# uno.net
KiCad netlist of a schematic drawn in EAGLE
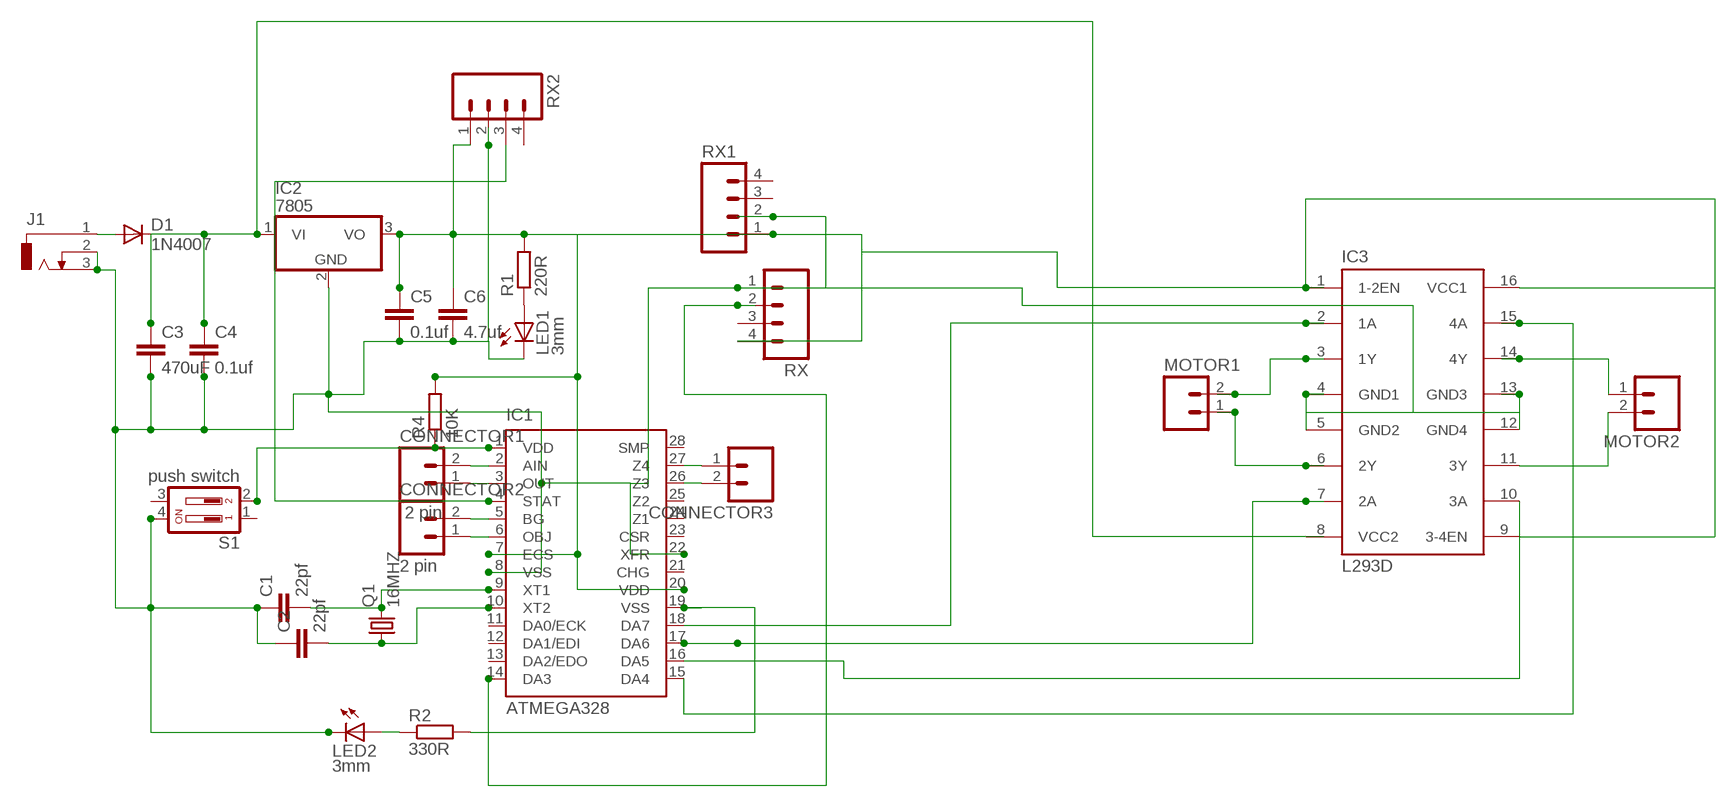
[diagram p0: schematic, sheet 1]

(export (version "E")
  (design (tool "Eeschema 10.0.6"))
  (components
    (comp (ref "C1")
      (value "22pf")
      (footprint "eagle-import:C2.5-2")
      (libsource (lib "eagle-import") (part "C2.5/2"))
    )
    (comp (ref "C2")
      (value "22pf")
      (footprint "eagle-import:C2.5-2")
      (libsource (lib "eagle-import") (part "C2.5/2"))
    )
    (comp (ref "C3")
      (value "470uF")
      (footprint "eagle-import:C2.5-2")
      (libsource (lib "eagle-import") (part "C2.5/2"))
    )
    (comp (ref "C4")
      (value "0.1uf")
      (footprint "eagle-import:C2.5-2")
      (libsource (lib "eagle-import") (part "C2.5/2"))
    )
    (comp (ref "C5")
      (value "0.1uf")
      (footprint "eagle-import:C2.5-2")
      (libsource (lib "eagle-import") (part "C2.5/2"))
    )
    (comp (ref "C6")
      (value "4.7uf")
      (footprint "eagle-import:C2.5-2")
      (libsource (lib "eagle-import") (part "C2.5/2"))
    )
    (comp (ref "CONNECTOR1")
      (value "2 pin")
      (footprint "eagle-import:02P")
      (fields (field (name "OC_FARNELL") "unknown") (field (name "OC_NEWARK") "unknown"))
      (libsource (lib "eagle-import") (part "M02"))
    )
    (comp (ref "CONNECTOR2")
      (value "2 pin")
      (footprint "eagle-import:02P")
      (fields (field (name "OC_FARNELL") "unknown") (field (name "OC_NEWARK") "unknown"))
      (libsource (lib "eagle-import") (part "M02"))
    )
    (comp (ref "CONNECTOR3")
      (value "M02")
      (footprint "eagle-import:02P")
      (fields (field (name "OC_FARNELL") "unknown") (field (name "OC_NEWARK") "unknown"))
      (libsource (lib "eagle-import") (part "M02"))
    )
    (comp (ref "D1")
      (value "1N4007")
      (footprint "eagle-import:DO41-10")
      (libsource (lib "eagle-import") (part "1N4004"))
    )
    (comp (ref "IC1")
      (value "ATMEGA328")
      (footprint "eagle-import:DIL28-3")
      (libsource (lib "eagle-import") (part "QT9701BD"))
    )
    (comp (ref "IC2")
      (value "7805")
      (footprint "eagle-import:TO220V")
      (libsource (lib "eagle-import") (part "78TV6"))
    )
    (comp (ref "IC3")
      (value "L293D")
      (footprint "eagle-import:DIL16")
      (libsource (lib "eagle-import") (part "L293D"))
    )
    (comp (ref "J1")
      (value "DCJ0303")
      (footprint "eagle-import:DCJ0303")
      (libsource (lib "eagle-import") (part "DCJ0303"))
    )
    (comp (ref "LED1")
      (value "3mm")
      (footprint "eagle-import:LED3MM")
      (libsource (lib "eagle-import") (part "LED3MM"))
    )
    (comp (ref "LED2")
      (value "3mm")
      (footprint "eagle-import:LED3MM")
      (libsource (lib "eagle-import") (part "LED3MM"))
    )
    (comp (ref "MOTOR1")
      (value "M02")
      (footprint "eagle-import:02P")
      (fields (field (name "OC_FARNELL") "unknown") (field (name "OC_NEWARK") "unknown"))
      (libsource (lib "eagle-import") (part "M02"))
    )
    (comp (ref "MOTOR2")
      (value "M02")
      (footprint "eagle-import:02P")
      (libsource (lib "eagle-import") (part "M02"))
    )
    (comp (ref "Q1")
      (value "16MHZ")
      (footprint "eagle-import:HC49_S")
      (libsource (lib "eagle-import") (part "CRYSTALHC49S"))
    )
    (comp (ref "R1")
      (value "220R")
      (footprint "eagle-import:0207_10")
      (libsource (lib "eagle-import") (part "R-EU_0207/10"))
    )
    (comp (ref "R2")
      (value "330R")
      (footprint "eagle-import:0207_10")
      (libsource (lib "eagle-import") (part "R-EU_0207/10"))
    )
    (comp (ref "R4")
      (value "10K")
      (footprint "eagle-import:0207_10")
      (libsource (lib "eagle-import") (part "R-EU_0207/10"))
    )
    (comp (ref "RX")
      (value "M04")
      (footprint "eagle-import:04P")
      (libsource (lib "eagle-import") (part "M04"))
    )
    (comp (ref "RX1")
      (value "M04")
      (footprint "eagle-import:04P")
      (fields (field (name "OC_FARNELL") "unknown") (field (name "OC_NEWARK") "unknown"))
      (libsource (lib "eagle-import") (part "M04"))
    )
    (comp (ref "RX2")
      (value "M04")
      (footprint "eagle-import:04P")
      (fields (field (name "OC_FARNELL") "unknown") (field (name "OC_NEWARK") "unknown"))
      (libsource (lib "eagle-import") (part "M04"))
    )
    (comp (ref "S1")
      (value "push switch")
      (footprint "eagle-import:DP-02")
      (fields (field (name "MPN") "MCDP02"))
      (libsource (lib "eagle-import") (part "DP02"))
    )
  )
  (nets
    (net (code "1") (name "Net-(D1-PadA)") (class "Default")
      (node (ref "D1") (pin "A") (pinfunction "A_A") (pintype "passive"))
      (node (ref "J1") (pin "1") (pinfunction "1_1") (pintype "passive"))
    )
    (net (code "2") (name "Net-(IC1-AIN)") (class "Default")
      (node (ref "CONNECTOR1") (pin "2") (pinfunction "2_2") (pintype "passive"))
      (node (ref "IC1") (pin "2") (pinfunction "AIN_2") (pintype "input"))
    )
    (net (code "3") (name "Net-(IC1-BG)") (class "Default")
      (node (ref "CONNECTOR2") (pin "2") (pinfunction "2_2") (pintype "passive"))
      (node (ref "IC1") (pin "5") (pinfunction "BG_5") (pintype "input"))
    )
    (net (code "4") (name "Net-(IC1-DA3)") (class "Default")
      (node (ref "IC1") (pin "14") (pinfunction "DA3_14") (pintype "output"))
      (node (ref "RX") (pin "2") (pinfunction "2_2") (pintype "passive"))
    )
    (net (code "5") (name "Net-(IC1-DA4)") (class "Default")
      (node (ref "IC1") (pin "15") (pinfunction "DA4_15") (pintype "output"))
      (node (ref "IC3") (pin "15") (pinfunction "4A_15") (pintype "input"))
    )
    (net (code "6") (name "Net-(IC1-DA5)") (class "Default")
      (node (ref "IC1") (pin "16") (pinfunction "DA5_16") (pintype "output"))
      (node (ref "IC3") (pin "10") (pinfunction "3A_10") (pintype "input"))
    )
    (net (code "7") (name "Net-(IC1-DA6)") (class "Default")
      (node (ref "IC1") (pin "17") (pinfunction "DA6_17") (pintype "output"))
      (node (ref "IC3") (pin "7") (pinfunction "2A_7") (pintype "input"))
    )
    (net (code "8") (name "Net-(IC1-DA7)") (class "Default")
      (node (ref "IC1") (pin "18") (pinfunction "DA7_18") (pintype "output"))
      (node (ref "IC3") (pin "2") (pinfunction "1A_2") (pintype "input"))
    )
    (net (code "9") (name "Net-(IC1-ECS)") (class "Default")
      (node (ref "C5") (pin "1") (pinfunction "1_1") (pintype "passive"))
      (node (ref "C6") (pin "1") (pinfunction "1_1") (pintype "passive"))
      (node (ref "IC1") (pin "20") (pinfunction "VDD_20") (pintype "input"))
      (node (ref "IC1") (pin "7") (pinfunction "ECS_7") (pintype "output"))
      (node (ref "IC2") (pin "3") (pinfunction "VO_3") (pintype "passive"))
      (node (ref "IC3") (pin "1") (pinfunction "1-2EN_1") (pintype "input"))
      (node (ref "IC3") (pin "16") (pinfunction "VCC1_16") (pintype "power_in"))
      (node (ref "IC3") (pin "9") (pinfunction "3-4EN_9") (pintype "input"))
      (node (ref "R1") (pin "2") (pinfunction "2_2") (pintype "passive"))
      (node (ref "R4") (pin "2") (pinfunction "2_2") (pintype "passive"))
      (node (ref "RX") (pin "4") (pinfunction "4_4") (pintype "passive"))
      (node (ref "RX1") (pin "1") (pinfunction "1_1") (pintype "passive"))
      (node (ref "RX2") (pin "1") (pinfunction "1_1") (pintype "passive"))
    )
    (net (code "10") (name "Net-(IC1-OBJ)") (class "Default")
      (node (ref "CONNECTOR2") (pin "1") (pinfunction "1_1") (pintype "passive"))
      (node (ref "IC1") (pin "6") (pinfunction "OBJ_6") (pintype "input"))
    )
    (net (code "11") (name "Net-(IC1-OUT)") (class "Default")
      (node (ref "CONNECTOR1") (pin "1") (pinfunction "1_1") (pintype "passive"))
      (node (ref "IC1") (pin "3") (pinfunction "OUT_3") (pintype "output"))
    )
    (net (code "12") (name "Net-(IC1-STAT)") (class "Default")
      (node (ref "IC1") (pin "4") (pinfunction "STAT_4") (pintype "output"))
      (node (ref "RX2") (pin "3") (pinfunction "3_3") (pintype "passive"))
    )
    (net (code "13") (name "Net-(IC1-VDD-Pad1)") (class "Default")
      (node (ref "IC1") (pin "1") (pinfunction "VDD_1") (pintype "input"))
      (node (ref "R4") (pin "1") (pinfunction "1_1") (pintype "passive"))
      (node (ref "S1") (pin "2") (pinfunction "2_2") (pintype "passive"))
    )
    (net (code "14") (name "Net-(IC1-VSS-Pad19)") (class "Default")
      (node (ref "IC1") (pin "19") (pinfunction "VSS_19") (pintype "input"))
      (node (ref "R2") (pin "2") (pinfunction "2_2") (pintype "passive"))
    )
    (net (code "15") (name "Net-(IC1-XFR)") (class "Default")
      (node (ref "C1") (pin "1") (pinfunction "1_1") (pintype "passive"))
      (node (ref "C2") (pin "1") (pinfunction "1_1") (pintype "passive"))
      (node (ref "C3") (pin "2") (pinfunction "2_2") (pintype "passive"))
      (node (ref "C4") (pin "2") (pinfunction "2_2") (pintype "passive"))
      (node (ref "C5") (pin "2") (pinfunction "2_2") (pintype "passive"))
      (node (ref "C6") (pin "2") (pinfunction "2_2") (pintype "passive"))
      (node (ref "IC1") (pin "22") (pinfunction "XFR_22") (pintype "output"))
      (node (ref "IC1") (pin "8") (pinfunction "VSS_8") (pintype "input"))
      (node (ref "IC2") (pin "2") (pinfunction "GND_2") (pintype "passive"))
      (node (ref "IC3") (pin "12") (pinfunction "GND4_12") (pintype "power_in"))
      (node (ref "IC3") (pin "13") (pinfunction "GND3_13") (pintype "power_in"))
      (node (ref "IC3") (pin "4") (pinfunction "GND1_4") (pintype "power_in"))
      (node (ref "IC3") (pin "5") (pinfunction "GND2_5") (pintype "power_in"))
      (node (ref "J1") (pin "2") (pinfunction "2_2") (pintype "passive"))
      (node (ref "J1") (pin "3") (pinfunction "3_3") (pintype "passive"))
      (node (ref "LED1") (pin "K") (pinfunction "C_K") (pintype "passive"))
      (node (ref "LED2") (pin "K") (pinfunction "C_K") (pintype "passive"))
      (node (ref "RX") (pin "1") (pinfunction "1_1") (pintype "passive"))
      (node (ref "RX1") (pin "2") (pinfunction "2_2") (pintype "passive"))
      (node (ref "RX2") (pin "2") (pinfunction "2_2") (pintype "passive"))
      (node (ref "S1") (pin "4") (pinfunction "4_4") (pintype "passive"))
    )
    (net (code "16") (name "Net-(IC1-XT1)") (class "Default")
      (node (ref "C1") (pin "2") (pinfunction "2_2") (pintype "passive"))
      (node (ref "IC1") (pin "9") (pinfunction "XT1_9") (pintype "input"))
      (node (ref "Q1") (pin "2") (pinfunction "2_2") (pintype "passive"))
    )
    (net (code "17") (name "Net-(IC1-XT2)") (class "Default")
      (node (ref "C2") (pin "2") (pinfunction "2_2") (pintype "passive"))
      (node (ref "IC1") (pin "10") (pinfunction "XT2_10") (pintype "output"))
      (node (ref "Q1") (pin "1") (pinfunction "1_1") (pintype "passive"))
    )
    (net (code "18") (name "Net-(IC1-Z3)") (class "Default")
      (node (ref "CONNECTOR3") (pin "2") (pinfunction "2_2") (pintype "passive"))
      (node (ref "IC1") (pin "26") (pinfunction "Z3_26") (pintype "output"))
    )
    (net (code "19") (name "Net-(IC1-Z4)") (class "Default")
      (node (ref "CONNECTOR3") (pin "1") (pinfunction "1_1") (pintype "passive"))
      (node (ref "IC1") (pin "27") (pinfunction "Z4_27") (pintype "output"))
    )
    (net (code "20") (name "Net-(IC2-VI)") (class "Default")
      (node (ref "C3") (pin "1") (pinfunction "1_1") (pintype "passive"))
      (node (ref "C4") (pin "1") (pinfunction "1_1") (pintype "passive"))
      (node (ref "D1") (pin "C") (pinfunction "C_C") (pintype "passive"))
      (node (ref "IC2") (pin "1") (pinfunction "VI_1") (pintype "input"))
      (node (ref "IC3") (pin "8") (pinfunction "VCC2_8") (pintype "power_in"))
    )
    (net (code "21") (name "Net-(IC3-1Y)") (class "Default")
      (node (ref "IC3") (pin "3") (pinfunction "1Y_3") (pintype "output"))
      (node (ref "MOTOR1") (pin "2") (pinfunction "2_2") (pintype "passive"))
    )
    (net (code "22") (name "Net-(IC3-2Y)") (class "Default")
      (node (ref "IC3") (pin "6") (pinfunction "2Y_6") (pintype "output"))
      (node (ref "MOTOR1") (pin "1") (pinfunction "1_1") (pintype "passive"))
    )
    (net (code "23") (name "Net-(IC3-3Y)") (class "Default")
      (node (ref "IC3") (pin "11") (pinfunction "3Y_11") (pintype "output"))
      (node (ref "MOTOR2") (pin "2") (pinfunction "2_2") (pintype "passive"))
    )
    (net (code "24") (name "Net-(IC3-4Y)") (class "Default")
      (node (ref "IC3") (pin "14") (pinfunction "4Y_14") (pintype "output"))
      (node (ref "MOTOR2") (pin "1") (pinfunction "1_1") (pintype "passive"))
    )
    (net (code "25") (name "Net-(LED1-PadA)") (class "Default")
      (node (ref "LED1") (pin "A") (pinfunction "A_A") (pintype "passive"))
      (node (ref "R1") (pin "1") (pinfunction "1_1") (pintype "passive"))
    )
    (net (code "26") (name "Net-(LED2-PadA)") (class "Default")
      (node (ref "LED2") (pin "A") (pinfunction "A_A") (pintype "passive"))
      (node (ref "R2") (pin "1") (pinfunction "1_1") (pintype "passive"))
    )
    (net (code "27") (name "unconnected-(IC1-CHG-Pad21)") (class "Default")
      (node (ref "IC1") (pin "21") (pinfunction "CHG_21") (pintype "output"))
    )
    (net (code "28") (name "unconnected-(IC1-CSR-Pad23)") (class "Default")
      (node (ref "IC1") (pin "23") (pinfunction "CSR_23") (pintype "output"))
    )
    (net (code "29") (name "unconnected-(IC1-DA0{slash}ECK-Pad11)") (class "Default")
      (node (ref "IC1") (pin "11") (pinfunction "DA0/ECK_11") (pintype "output"))
    )
    (net (code "30") (name "unconnected-(IC1-DA1{slash}EDI-Pad12)") (class "Default")
      (node (ref "IC1") (pin "12") (pinfunction "DA1/EDI_12") (pintype "output"))
    )
    (net (code "31") (name "unconnected-(IC1-DA2{slash}EDO-Pad13)") (class "Default")
      (node (ref "IC1") (pin "13") (pinfunction "DA2/EDO_13") (pintype "output"))
    )
    (net (code "32") (name "unconnected-(IC1-SMP-Pad28)") (class "Default")
      (node (ref "IC1") (pin "28") (pinfunction "SMP_28") (pintype "output"))
    )
    (net (code "33") (name "unconnected-(IC1-Z1-Pad24)") (class "Default")
      (node (ref "IC1") (pin "24") (pinfunction "Z1_24") (pintype "output"))
    )
    (net (code "34") (name "unconnected-(IC1-Z2-Pad25)") (class "Default")
      (node (ref "IC1") (pin "25") (pinfunction "Z2_25") (pintype "output"))
    )
    (net (code "35") (name "unconnected-(RX-Pad3)") (class "Default")
      (node (ref "RX") (pin "3") (pinfunction "3_3") (pintype "passive"))
    )
    (net (code "36") (name "unconnected-(RX1-Pad3)") (class "Default")
      (node (ref "RX1") (pin "3") (pinfunction "3_3") (pintype "passive"))
    )
    (net (code "37") (name "unconnected-(RX1-Pad4)") (class "Default")
      (node (ref "RX1") (pin "4") (pinfunction "4_4") (pintype "passive"))
    )
    (net (code "38") (name "unconnected-(RX2-Pad4)") (class "Default")
      (node (ref "RX2") (pin "4") (pinfunction "4_4") (pintype "passive"))
    )
    (net (code "39") (name "unconnected-(S1-Pad1)") (class "Default")
      (node (ref "S1") (pin "1") (pinfunction "1_1") (pintype "passive"))
    )
    (net (code "40") (name "unconnected-(S1-Pad3)") (class "Default")
      (node (ref "S1") (pin "3") (pinfunction "3_3") (pintype "passive"))
    )
  )
)
